# Processor.net
KiCad netlist of a schematic drawn in Altium Designer
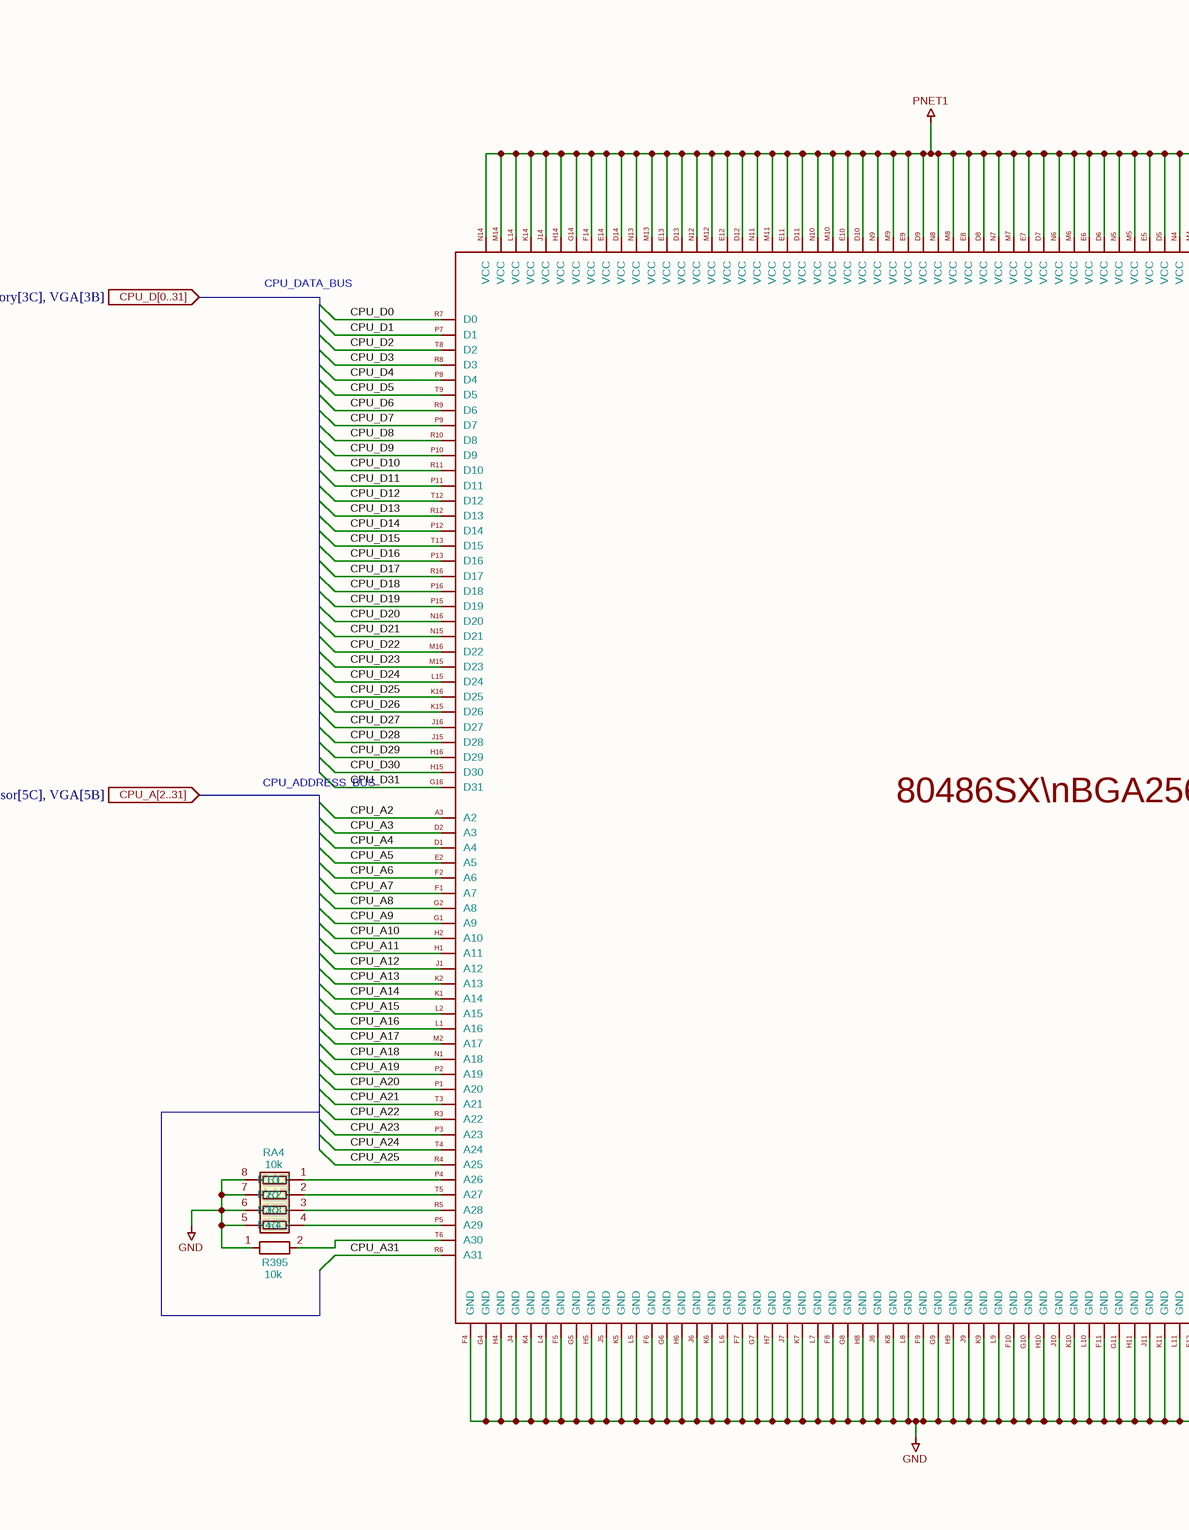
[diagram p0: Processor.SchDoc, left]
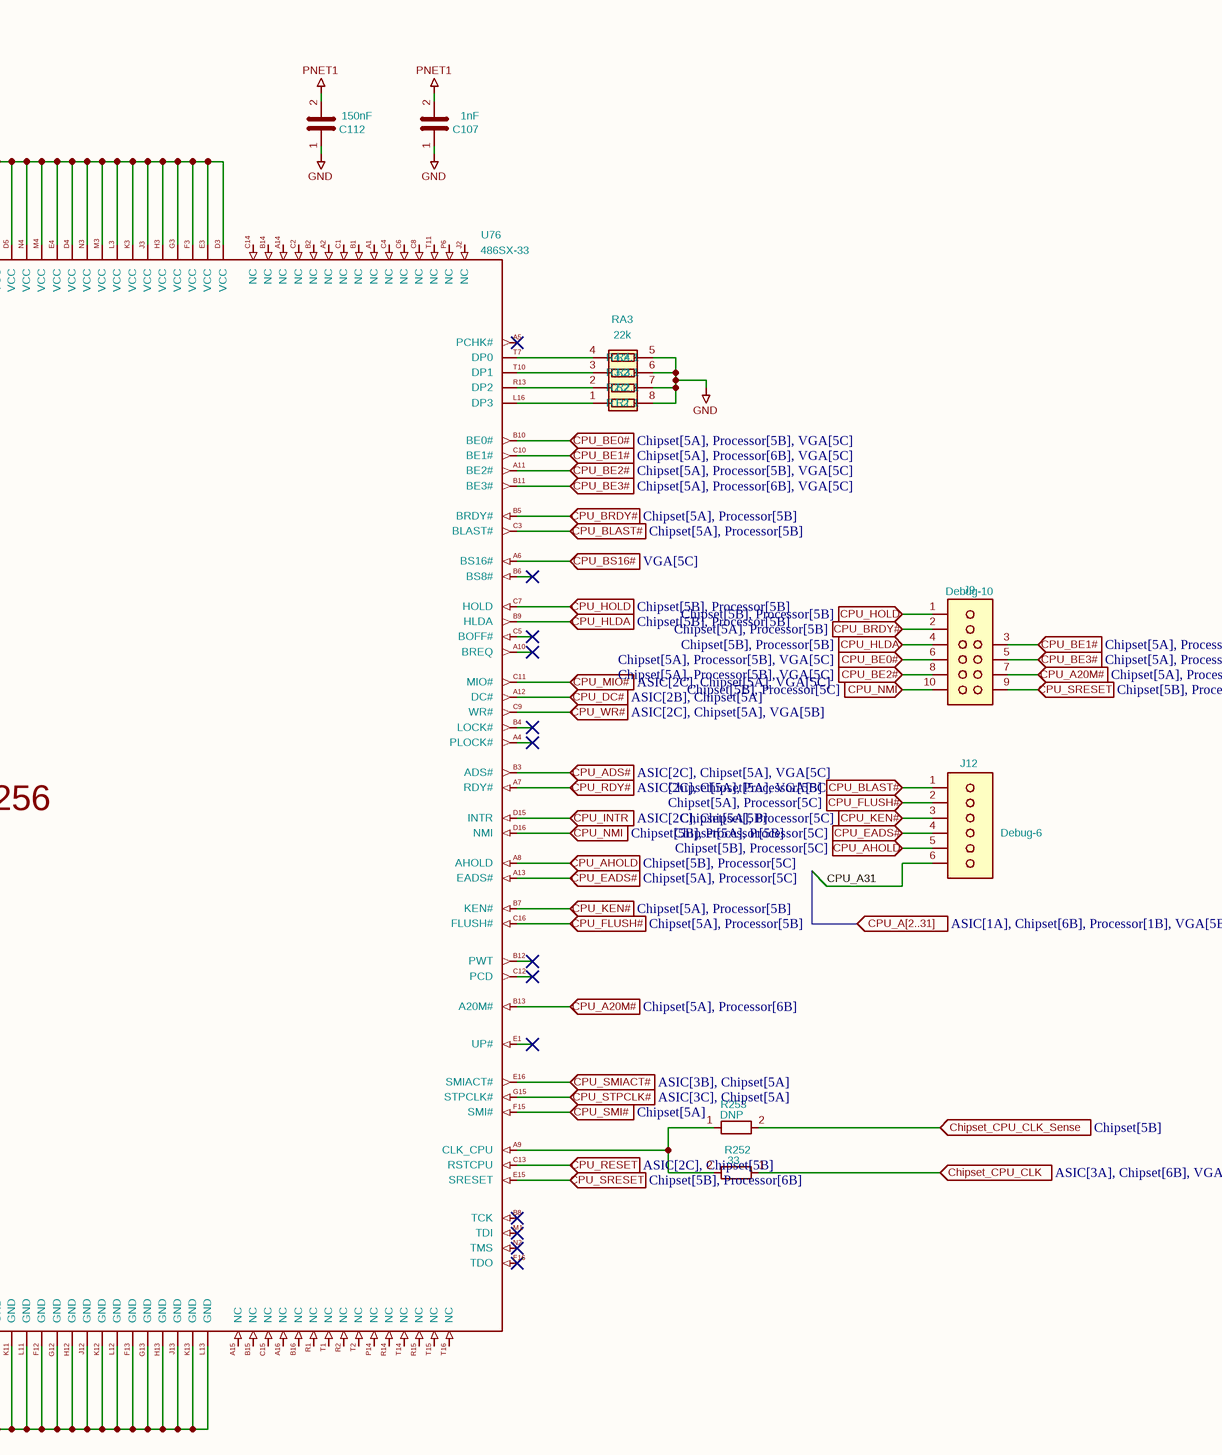
[diagram p1: Processor.SchDoc, right]

(export (version "E")
  (design (tool "Eeschema 10.0.6"))
  (components
    (comp (ref "C107") (value "1nF") (footprint "C_0402_1005Metric") (libsource (lib "Device") (part "C")))
    (comp (ref "C112") (value "150nF") (footprint "C_0402_1005Metric") (libsource (lib "Device") (part "C")))
    (comp (ref "J9") (value "Debug-10") (footprint "Debug-10") (libsource (lib "PC110") (part "CPU_Debug10")))
    (comp (ref "J12") (value "Debug-6") (footprint "Debug-6") (libsource (lib "PC110") (part "CPU_Debug6")))
    (comp (ref "R252") (value "33") (footprint "R_0402_1005Metric") (libsource (lib "Device") (part "R")))
    (comp (ref "R253") (value "DNP") (footprint "R_0402_1005Metric") (libsource (lib "") (part "R_1")))
    (comp (ref "R395") (value "10k") (footprint "R_0402_1005Metric") (libsource (lib "") (part "R_2")))
    (comp (ref "RA3") (value "22k") (footprint "R-array") (libsource (lib "Device") (part "R_Pack04")))
    (comp (ref "RA4") (value "10k") (footprint "R-array") (libsource (lib "") (part "R_Pack04_1")))
    (comp (ref "U76") (value "486SX-33") (footprint "BGA-256") (libsource (lib "PC110") (part "80486SX")))
  )
  (nets
    (net (code "6") (name "/CPU_A2") (class "Default")
      (node (ref "U76") (pin "A3") (pinfunction "A2_A3") (pintype "bidirectional"))
    )
    (net (code "7") (name "/CPU_A3") (class "Default")
      (node (ref "U76") (pin "D2") (pinfunction "A3_D2") (pintype "bidirectional"))
    )
    (net (code "8") (name "/CPU_A4") (class "Default")
      (node (ref "U76") (pin "D1") (pinfunction "A4_D1") (pintype "bidirectional"))
    )
    (net (code "9") (name "/CPU_A5") (class "Default")
      (node (ref "U76") (pin "E2") (pinfunction "A5_E2") (pintype "bidirectional"))
    )
    (net (code "10") (name "/CPU_A6") (class "Default")
      (node (ref "U76") (pin "F2") (pinfunction "A6_F2") (pintype "bidirectional"))
    )
    (net (code "11") (name "/CPU_A7") (class "Default")
      (node (ref "U76") (pin "F1") (pinfunction "A7_F1") (pintype "bidirectional"))
    )
    (net (code "12") (name "/CPU_A8") (class "Default")
      (node (ref "U76") (pin "G2") (pinfunction "A8_G2") (pintype "bidirectional"))
    )
    (net (code "13") (name "/CPU_A9") (class "Default")
      (node (ref "U76") (pin "G1") (pinfunction "A9_G1") (pintype "bidirectional"))
    )
    (net (code "14") (name "/CPU_A10") (class "Default")
      (node (ref "U76") (pin "H2") (pinfunction "A10_H2") (pintype "bidirectional"))
    )
    (net (code "15") (name "/CPU_A11") (class "Default")
      (node (ref "U76") (pin "H1") (pinfunction "A11_H1") (pintype "bidirectional"))
    )
    (net (code "16") (name "/CPU_A12") (class "Default")
      (node (ref "U76") (pin "J1") (pinfunction "A12_J1") (pintype "bidirectional"))
    )
    (net (code "17") (name "/CPU_A13") (class "Default")
      (node (ref "U76") (pin "K2") (pinfunction "A13_K2") (pintype "bidirectional"))
    )
    (net (code "18") (name "/CPU_A14") (class "Default")
      (node (ref "U76") (pin "K1") (pinfunction "A14_K1") (pintype "bidirectional"))
    )
    (net (code "19") (name "/CPU_A15") (class "Default")
      (node (ref "U76") (pin "L2") (pinfunction "A15_L2") (pintype "bidirectional"))
    )
    (net (code "20") (name "/CPU_A16") (class "Default")
      (node (ref "U76") (pin "L1") (pinfunction "A16_L1") (pintype "bidirectional"))
    )
    (net (code "21") (name "/CPU_A17") (class "Default")
      (node (ref "U76") (pin "M2") (pinfunction "A17_M2") (pintype "bidirectional"))
    )
    (net (code "22") (name "/CPU_A18") (class "Default")
      (node (ref "U76") (pin "N1") (pinfunction "A18_N1") (pintype "bidirectional"))
    )
    (net (code "23") (name "/CPU_A19") (class "Default")
      (node (ref "U76") (pin "P2") (pinfunction "A19_P2") (pintype "bidirectional"))
    )
    (net (code "24") (name "/CPU_A20") (class "Default")
      (node (ref "U76") (pin "P1") (pinfunction "A20_P1") (pintype "bidirectional"))
    )
    (net (code "25") (name "/CPU_A20M#") (class "Default")
      (node (ref "J9") (pin "7") (pinfunction "7_7") (pintype "passive"))
      (node (ref "U76") (pin "B13") (pinfunction "A20M#_B13") (pintype "input"))
    )
    (net (code "26") (name "/CPU_A21") (class "Default")
      (node (ref "U76") (pin "T3") (pinfunction "A21_T3") (pintype "bidirectional"))
    )
    (net (code "27") (name "/CPU_A22") (class "Default")
      (node (ref "U76") (pin "R3") (pinfunction "A22_R3") (pintype "bidirectional"))
    )
    (net (code "28") (name "/CPU_A23") (class "Default")
      (node (ref "U76") (pin "P3") (pinfunction "A23_P3") (pintype "bidirectional"))
    )
    (net (code "29") (name "/CPU_A24") (class "Default")
      (node (ref "U76") (pin "T4") (pinfunction "A24_T4") (pintype "bidirectional"))
    )
    (net (code "30") (name "/CPU_A25") (class "Default")
      (node (ref "U76") (pin "R4") (pinfunction "A25_R4") (pintype "bidirectional"))
    )
    (net (code "31") (name "/CPU_A31") (class "Default")
      (node (ref "J12") (pin "6") (pinfunction "6_6") (pintype "passive"))
      (node (ref "U76") (pin "R6") (pinfunction "A31_R6") (pintype "bidirectional"))
    )
    (net (code "32") (name "/CPU_ADS#") (class "Default")
      (node (ref "U76") (pin "B3") (pinfunction "ADS#_B3") (pintype "output"))
    )
    (net (code "33") (name "/CPU_AHOLD") (class "Default")
      (node (ref "J12") (pin "5") (pinfunction "5_5") (pintype "passive"))
      (node (ref "U76") (pin "A8") (pinfunction "AHOLD_A8") (pintype "input"))
    )
    (net (code "35") (name "/CPU_BE0#") (class "Default")
      (node (ref "J9") (pin "6") (pinfunction "6_6") (pintype "passive"))
      (node (ref "U76") (pin "B10") (pinfunction "BE0#_B10") (pintype "output"))
    )
    (net (code "36") (name "/CPU_BE1#") (class "Default")
      (node (ref "J9") (pin "3") (pinfunction "3_3") (pintype "passive"))
      (node (ref "U76") (pin "C10") (pinfunction "BE1#_C10") (pintype "output"))
    )
    (net (code "37") (name "/CPU_BE2#") (class "Default")
      (node (ref "J9") (pin "8") (pinfunction "8_8") (pintype "passive"))
      (node (ref "U76") (pin "A11") (pinfunction "BE2#_A11") (pintype "output"))
    )
    (net (code "38") (name "/CPU_BE3#") (class "Default")
      (node (ref "J9") (pin "5") (pinfunction "5_5") (pintype "passive"))
      (node (ref "U76") (pin "B11") (pinfunction "BE3#_B11") (pintype "output"))
    )
    (net (code "39") (name "/CPU_BLAST#") (class "Default")
      (node (ref "J12") (pin "1") (pinfunction "1_1") (pintype "passive"))
      (node (ref "U76") (pin "C3") (pinfunction "BLAST#_C3") (pintype "output"))
    )
    (net (code "40") (name "/CPU_BRDY#") (class "Default")
      (node (ref "J9") (pin "2") (pinfunction "2_2") (pintype "passive"))
      (node (ref "U76") (pin "B5") (pinfunction "BRDY#_B5") (pintype "input"))
    )
    (net (code "41") (name "/CPU_BS16#") (class "Default")
      (node (ref "U76") (pin "A6") (pinfunction "BS16#_A6") (pintype "input"))
    )
    (net (code "42") (name "/CPU_D0") (class "Default")
      (node (ref "U76") (pin "R7") (pinfunction "D0_R7") (pintype "bidirectional"))
    )
    (net (code "43") (name "/CPU_D1") (class "Default")
      (node (ref "U76") (pin "P7") (pinfunction "D1_P7") (pintype "bidirectional"))
    )
    (net (code "44") (name "/CPU_D2") (class "Default")
      (node (ref "U76") (pin "T8") (pinfunction "D2_T8") (pintype "bidirectional"))
    )
    (net (code "45") (name "/CPU_D3") (class "Default")
      (node (ref "U76") (pin "R8") (pinfunction "D3_R8") (pintype "bidirectional"))
    )
    (net (code "46") (name "/CPU_D4") (class "Default")
      (node (ref "U76") (pin "P8") (pinfunction "D4_P8") (pintype "bidirectional"))
    )
    (net (code "47") (name "/CPU_D5") (class "Default")
      (node (ref "U76") (pin "T9") (pinfunction "D5_T9") (pintype "bidirectional"))
    )
    (net (code "48") (name "/CPU_D6") (class "Default")
      (node (ref "U76") (pin "R9") (pinfunction "D6_R9") (pintype "bidirectional"))
    )
    (net (code "49") (name "/CPU_D7") (class "Default")
      (node (ref "U76") (pin "P9") (pinfunction "D7_P9") (pintype "bidirectional"))
    )
    (net (code "50") (name "/CPU_D8") (class "Default")
      (node (ref "U76") (pin "R10") (pinfunction "D8_R10") (pintype "bidirectional"))
    )
    (net (code "51") (name "/CPU_D9") (class "Default")
      (node (ref "U76") (pin "P10") (pinfunction "D9_P10") (pintype "bidirectional"))
    )
    (net (code "52") (name "/CPU_D10") (class "Default")
      (node (ref "U76") (pin "R11") (pinfunction "D10_R11") (pintype "bidirectional"))
    )
    (net (code "53") (name "/CPU_D11") (class "Default")
      (node (ref "U76") (pin "P11") (pinfunction "D11_P11") (pintype "bidirectional"))
    )
    (net (code "54") (name "/CPU_D12") (class "Default")
      (node (ref "U76") (pin "T12") (pinfunction "D12_T12") (pintype "bidirectional"))
    )
    (net (code "55") (name "/CPU_D13") (class "Default")
      (node (ref "U76") (pin "R12") (pinfunction "D13_R12") (pintype "bidirectional"))
    )
    (net (code "56") (name "/CPU_D14") (class "Default")
      (node (ref "U76") (pin "P12") (pinfunction "D14_P12") (pintype "bidirectional"))
    )
    (net (code "57") (name "/CPU_D15") (class "Default")
      (node (ref "U76") (pin "T13") (pinfunction "D15_T13") (pintype "bidirectional"))
    )
    (net (code "58") (name "/CPU_D16") (class "Default")
      (node (ref "U76") (pin "P13") (pinfunction "D16_P13") (pintype "bidirectional"))
    )
    (net (code "59") (name "/CPU_D17") (class "Default")
      (node (ref "U76") (pin "R16") (pinfunction "D17_R16") (pintype "bidirectional"))
    )
    (net (code "60") (name "/CPU_D18") (class "Default")
      (node (ref "U76") (pin "P16") (pinfunction "D18_P16") (pintype "bidirectional"))
    )
    (net (code "61") (name "/CPU_D19") (class "Default")
      (node (ref "U76") (pin "P15") (pinfunction "D19_P15") (pintype "bidirectional"))
    )
    (net (code "62") (name "/CPU_D20") (class "Default")
      (node (ref "U76") (pin "N16") (pinfunction "D20_N16") (pintype "bidirectional"))
    )
    (net (code "63") (name "/CPU_D21") (class "Default")
      (node (ref "U76") (pin "N15") (pinfunction "D21_N15") (pintype "bidirectional"))
    )
    (net (code "64") (name "/CPU_D22") (class "Default")
      (node (ref "U76") (pin "M16") (pinfunction "D22_M16") (pintype "bidirectional"))
    )
    (net (code "65") (name "/CPU_D23") (class "Default")
      (node (ref "U76") (pin "M15") (pinfunction "D23_M15") (pintype "bidirectional"))
    )
    (net (code "66") (name "/CPU_D24") (class "Default")
      (node (ref "U76") (pin "L15") (pinfunction "D24_L15") (pintype "bidirectional"))
    )
    (net (code "67") (name "/CPU_D25") (class "Default")
      (node (ref "U76") (pin "K16") (pinfunction "D25_K16") (pintype "bidirectional"))
    )
    (net (code "68") (name "/CPU_D26") (class "Default")
      (node (ref "U76") (pin "K15") (pinfunction "D26_K15") (pintype "bidirectional"))
    )
    (net (code "69") (name "/CPU_D27") (class "Default")
      (node (ref "U76") (pin "J16") (pinfunction "D27_J16") (pintype "bidirectional"))
    )
    (net (code "70") (name "/CPU_D28") (class "Default")
      (node (ref "U76") (pin "J15") (pinfunction "D28_J15") (pintype "bidirectional"))
    )
    (net (code "71") (name "/CPU_D29") (class "Default")
      (node (ref "U76") (pin "H16") (pinfunction "D29_H16") (pintype "bidirectional"))
    )
    (net (code "72") (name "/CPU_D30") (class "Default")
      (node (ref "U76") (pin "H15") (pinfunction "D30_H15") (pintype "bidirectional"))
    )
    (net (code "73") (name "/CPU_D31") (class "Default")
      (node (ref "U76") (pin "G16") (pinfunction "D31_G16") (pintype "bidirectional"))
    )
    (net (code "74") (name "/CPU_DC#") (class "Default")
      (node (ref "U76") (pin "A12") (pinfunction "DC#_A12") (pintype "output"))
    )
    (net (code "76") (name "/CPU_EADS#") (class "Default")
      (node (ref "J12") (pin "4") (pinfunction "4_4") (pintype "passive"))
      (node (ref "U76") (pin "A13") (pinfunction "EADS#_A13") (pintype "input"))
    )
    (net (code "77") (name "/CPU_FLUSH#") (class "Default")
      (node (ref "J12") (pin "2") (pinfunction "2_2") (pintype "passive"))
      (node (ref "U76") (pin "C16") (pinfunction "FLUSH#_C16") (pintype "input"))
    )
    (net (code "78") (name "/CPU_HLDA") (class "Default")
      (node (ref "J9") (pin "4") (pinfunction "4_4") (pintype "passive"))
      (node (ref "U76") (pin "B9") (pinfunction "HLDA_B9") (pintype "output"))
    )
    (net (code "79") (name "/CPU_HOLD") (class "Default")
      (node (ref "J9") (pin "1") (pinfunction "1_1") (pintype "passive"))
      (node (ref "U76") (pin "C7") (pinfunction "HOLD_C7") (pintype "input"))
    )
    (net (code "80") (name "/CPU_INTR") (class "Default")
      (node (ref "U76") (pin "D15") (pinfunction "INTR_D15") (pintype "input"))
    )
    (net (code "81") (name "/CPU_KEN#") (class "Default")
      (node (ref "J12") (pin "3") (pinfunction "3_3") (pintype "passive"))
      (node (ref "U76") (pin "B7") (pinfunction "KEN#_B7") (pintype "input"))
    )
    (net (code "82") (name "/CPU_MIO#") (class "Default")
      (node (ref "U76") (pin "C11") (pinfunction "MIO#_C11") (pintype "output"))
    )
    (net (code "83") (name "/CPU_NMI") (class "Default")
      (node (ref "J9") (pin "10") (pinfunction "10_10") (pintype "passive"))
      (node (ref "U76") (pin "D16") (pinfunction "NMI_D16") (pintype "input"))
    )
    (net (code "84") (name "/CPU_RDY#") (class "Default")
      (node (ref "U76") (pin "A7") (pinfunction "RDY#_A7") (pintype "input"))
    )
    (net (code "85") (name "/CPU_RESET") (class "Default")
      (node (ref "U76") (pin "C13") (pinfunction "RSTCPU_C13") (pintype "input"))
    )
    (net (code "86") (name "/CPU_SMI#") (class "Default")
      (node (ref "U76") (pin "F15") (pinfunction "SMI#_F15") (pintype "input"))
    )
    (net (code "87") (name "/CPU_SMIACT#") (class "Default")
      (node (ref "U76") (pin "E16") (pinfunction "SMIACT#_E16") (pintype "output"))
    )
    (net (code "88") (name "/CPU_SRESET") (class "Default")
      (node (ref "J9") (pin "9") (pinfunction "9_9") (pintype "passive"))
      (node (ref "U76") (pin "E15") (pinfunction "SRESET_E15") (pintype "input"))
    )
    (net (code "89") (name "/CPU_STPCLK#") (class "Default")
      (node (ref "U76") (pin "G15") (pinfunction "STPCLK#_G15") (pintype "input"))
    )
    (net (code "90") (name "/CPU_WR#") (class "Default")
      (node (ref "U76") (pin "C9") (pinfunction "WR#_C9") (pintype "output"))
    )
    (net (code "91") (name "/Chipset_CPU_CLK") (class "Default")
      (node (ref "R252") (pin "1") (pinfunction "1_1") (pintype "passive"))
    )
    (net (code "92") (name "/Chipset_CPU_CLK_Sense") (class "Default")
      (node (ref "R253") (pin "2") (pinfunction "2_2") (pintype "passive"))
    )
    (net (code "93") (name "GND") (class "Default")
      (node (ref "C107") (pin "1") (pinfunction "1_1") (pintype "passive"))
      (node (ref "C112") (pin "1") (pinfunction "1_1") (pintype "passive"))
      (node (ref "R395") (pin "1") (pinfunction "1_1") (pintype "passive"))
      (node (ref "RA3") (pin "5") (pinfunction "R4.2_5") (pintype "passive"))
      (node (ref "RA3") (pin "6") (pinfunction "R3.2_6") (pintype "passive"))
      (node (ref "RA3") (pin "7") (pinfunction "R2.2_7") (pintype "passive"))
      (node (ref "RA3") (pin "8") (pinfunction "R1.2_8") (pintype "passive"))
      (node (ref "RA4") (pin "5") (pinfunction "R4.2_5") (pintype "passive"))
      (node (ref "RA4") (pin "6") (pinfunction "R3.2_6") (pintype "passive"))
      (node (ref "RA4") (pin "7") (pinfunction "R2.2_7") (pintype "passive"))
      (node (ref "RA4") (pin "8") (pinfunction "R1.2_8") (pintype "passive"))
      (node (ref "U76") (pin "F10") (pinfunction "GND_F10") (pintype "power_in"))
      (node (ref "U76") (pin "F11") (pinfunction "GND_F11") (pintype "power_in"))
      (node (ref "U76") (pin "F12") (pinfunction "GND_F12") (pintype "power_in"))
      (node (ref "U76") (pin "F13") (pinfunction "GND_F13") (pintype "power_in"))
      (node (ref "U76") (pin "F4") (pinfunction "GND_F4") (pintype "power_in"))
      (node (ref "U76") (pin "F5") (pinfunction "GND_F5") (pintype "power_in"))
      (node (ref "U76") (pin "F6") (pinfunction "GND_F6") (pintype "power_in"))
      (node (ref "U76") (pin "F7") (pinfunction "GND_F7") (pintype "power_in"))
      (node (ref "U76") (pin "F8") (pinfunction "GND_F8") (pintype "power_in"))
      (node (ref "U76") (pin "F9") (pinfunction "GND_F9") (pintype "power_in"))
      (node (ref "U76") (pin "G10") (pinfunction "GND_G10") (pintype "power_in"))
      (node (ref "U76") (pin "G11") (pinfunction "GND_G11") (pintype "power_in"))
      (node (ref "U76") (pin "G12") (pinfunction "GND_G12") (pintype "power_in"))
      (node (ref "U76") (pin "G13") (pinfunction "GND_G13") (pintype "power_in"))
      (node (ref "U76") (pin "G4") (pinfunction "GND_G4") (pintype "power_in"))
      (node (ref "U76") (pin "G5") (pinfunction "GND_G5") (pintype "power_in"))
      (node (ref "U76") (pin "G6") (pinfunction "GND_G6") (pintype "power_in"))
      (node (ref "U76") (pin "G7") (pinfunction "GND_G7") (pintype "power_in"))
      (node (ref "U76") (pin "G8") (pinfunction "GND_G8") (pintype "power_in"))
      (node (ref "U76") (pin "G9") (pinfunction "GND_G9") (pintype "power_in"))
      (node (ref "U76") (pin "H10") (pinfunction "GND_H10") (pintype "power_in"))
      (node (ref "U76") (pin "H11") (pinfunction "GND_H11") (pintype "power_in"))
      (node (ref "U76") (pin "H12") (pinfunction "GND_H12") (pintype "power_in"))
      (node (ref "U76") (pin "H13") (pinfunction "GND_H13") (pintype "power_in"))
      (node (ref "U76") (pin "H4") (pinfunction "GND_H4") (pintype "power_in"))
      (node (ref "U76") (pin "H5") (pinfunction "GND_H5") (pintype "power_in"))
      (node (ref "U76") (pin "H6") (pinfunction "GND_H6") (pintype "power_in"))
      (node (ref "U76") (pin "H7") (pinfunction "GND_H7") (pintype "power_in"))
      (node (ref "U76") (pin "H8") (pinfunction "GND_H8") (pintype "power_in"))
      (node (ref "U76") (pin "H9") (pinfunction "GND_H9") (pintype "power_in"))
      (node (ref "U76") (pin "J10") (pinfunction "GND_J10") (pintype "power_in"))
      (node (ref "U76") (pin "J11") (pinfunction "GND_J11") (pintype "power_in"))
      (node (ref "U76") (pin "J12") (pinfunction "GND_J12") (pintype "power_in"))
      (node (ref "U76") (pin "J13") (pinfunction "GND_J13") (pintype "power_in"))
      (node (ref "U76") (pin "J4") (pinfunction "GND_J4") (pintype "power_in"))
      (node (ref "U76") (pin "J5") (pinfunction "GND_J5") (pintype "power_in"))
      (node (ref "U76") (pin "J6") (pinfunction "GND_J6") (pintype "power_in"))
      (node (ref "U76") (pin "J7") (pinfunction "GND_J7") (pintype "power_in"))
      (node (ref "U76") (pin "J8") (pinfunction "GND_J8") (pintype "power_in"))
      (node (ref "U76") (pin "J9") (pinfunction "GND_J9") (pintype "power_in"))
      (node (ref "U76") (pin "K10") (pinfunction "GND_K10") (pintype "power_in"))
      (node (ref "U76") (pin "K11") (pinfunction "GND_K11") (pintype "power_in"))
      (node (ref "U76") (pin "K12") (pinfunction "GND_K12") (pintype "power_in"))
      (node (ref "U76") (pin "K13") (pinfunction "GND_K13") (pintype "power_in"))
      (node (ref "U76") (pin "K4") (pinfunction "GND_K4") (pintype "power_in"))
      (node (ref "U76") (pin "K5") (pinfunction "GND_K5") (pintype "power_in"))
      (node (ref "U76") (pin "K6") (pinfunction "GND_K6") (pintype "power_in"))
      (node (ref "U76") (pin "K7") (pinfunction "GND_K7") (pintype "power_in"))
      (node (ref "U76") (pin "K8") (pinfunction "GND_K8") (pintype "power_in"))
      (node (ref "U76") (pin "K9") (pinfunction "GND_K9") (pintype "power_in"))
      (node (ref "U76") (pin "L10") (pinfunction "GND_L10") (pintype "power_in"))
      (node (ref "U76") (pin "L11") (pinfunction "GND_L11") (pintype "power_in"))
      (node (ref "U76") (pin "L12") (pinfunction "GND_L12") (pintype "power_in"))
      (node (ref "U76") (pin "L13") (pinfunction "GND_L13") (pintype "power_in"))
      (node (ref "U76") (pin "L4") (pinfunction "GND_L4") (pintype "power_in"))
      (node (ref "U76") (pin "L5") (pinfunction "GND_L5") (pintype "power_in"))
      (node (ref "U76") (pin "L6") (pinfunction "GND_L6") (pintype "power_in"))
      (node (ref "U76") (pin "L7") (pinfunction "GND_L7") (pintype "power_in"))
      (node (ref "U76") (pin "L8") (pinfunction "GND_L8") (pintype "power_in"))
      (node (ref "U76") (pin "L9") (pinfunction "GND_L9") (pintype "power_in"))
    )
    (net (code "94") (name "Net-(RA3-R1.1)") (class "Default")
      (node (ref "RA3") (pin "1") (pinfunction "R1.1_1") (pintype "passive"))
      (node (ref "U76") (pin "L16") (pinfunction "DP3_L16") (pintype "bidirectional"))
    )
    (net (code "95") (name "Net-(RA3-R2.1)") (class "Default")
      (node (ref "RA3") (pin "2") (pinfunction "R2.1_2") (pintype "passive"))
      (node (ref "U76") (pin "R13") (pinfunction "DP2_R13") (pintype "bidirectional"))
    )
    (net (code "96") (name "Net-(RA3-R3.1)") (class "Default")
      (node (ref "RA3") (pin "3") (pinfunction "R3.1_3") (pintype "passive"))
      (node (ref "U76") (pin "T10") (pinfunction "DP1_T10") (pintype "bidirectional"))
    )
    (net (code "97") (name "Net-(RA3-R4.1)") (class "Default")
      (node (ref "RA3") (pin "4") (pinfunction "R4.1_4") (pintype "passive"))
      (node (ref "U76") (pin "T7") (pinfunction "DP0_T7") (pintype "bidirectional"))
    )
    (net (code "98") (name "Net-(RA4-R1.1)") (class "Default")
      (node (ref "RA4") (pin "1") (pinfunction "R1.1_1") (pintype "passive"))
      (node (ref "U76") (pin "P4") (pinfunction "A26_P4") (pintype "bidirectional"))
    )
    (net (code "99") (name "Net-(RA4-R2.1)") (class "Default")
      (node (ref "RA4") (pin "2") (pinfunction "R2.1_2") (pintype "passive"))
      (node (ref "U76") (pin "T5") (pinfunction "A27_T5") (pintype "bidirectional"))
    )
    (net (code "100") (name "Net-(RA4-R3.1)") (class "Default")
      (node (ref "RA4") (pin "3") (pinfunction "R3.1_3") (pintype "passive"))
      (node (ref "U76") (pin "R5") (pinfunction "A28_R5") (pintype "bidirectional"))
    )
    (net (code "101") (name "Net-(RA4-R4.1)") (class "Default")
      (node (ref "RA4") (pin "4") (pinfunction "R4.1_4") (pintype "passive"))
      (node (ref "U76") (pin "P5") (pinfunction "A29_P5") (pintype "bidirectional"))
    )
    (net (code "102") (name "Net-(U76-A30)") (class "Default")
      (node (ref "R395") (pin "2") (pinfunction "2_2") (pintype "passive"))
      (node (ref "U76") (pin "T6") (pinfunction "A30_T6") (pintype "bidirectional"))
    )
    (net (code "103") (name "Net-(U76-CLK_CPU)") (class "Default")
      (node (ref "R252") (pin "2") (pinfunction "2_2") (pintype "passive"))
      (node (ref "R253") (pin "1") (pinfunction "1_1") (pintype "passive"))
      (node (ref "U76") (pin "A9") (pinfunction "CLK_CPU_A9") (pintype "input"))
    )
    (net (code "104") (name "PNET1") (class "Default")
      (node (ref "C107") (pin "2") (pinfunction "2_2") (pintype "passive"))
      (node (ref "C112") (pin "2") (pinfunction "2_2") (pintype "passive"))
      (node (ref "U76") (pin "D10") (pinfunction "VCC_D10") (pintype "power_in"))
      (node (ref "U76") (pin "D11") (pinfunction "VCC_D11") (pintype "power_in"))
      (node (ref "U76") (pin "D12") (pinfunction "VCC_D12") (pintype "power_in"))
      (node (ref "U76") (pin "D13") (pinfunction "VCC_D13") (pintype "power_in"))
      (node (ref "U76") (pin "D14") (pinfunction "VCC_D14") (pintype "power_in"))
      (node (ref "U76") (pin "D3") (pinfunction "VCC_D3") (pintype "power_in"))
      (node (ref "U76") (pin "D4") (pinfunction "VCC_D4") (pintype "power_in"))
      (node (ref "U76") (pin "D5") (pinfunction "VCC_D5") (pintype "power_in"))
      (node (ref "U76") (pin "D6") (pinfunction "VCC_D6") (pintype "power_in"))
      (node (ref "U76") (pin "D7") (pinfunction "VCC_D7") (pintype "power_in"))
      (node (ref "U76") (pin "D8") (pinfunction "VCC_D8") (pintype "power_in"))
      (node (ref "U76") (pin "D9") (pinfunction "VCC_D9") (pintype "power_in"))
      (node (ref "U76") (pin "E10") (pinfunction "VCC_E10") (pintype "power_in"))
      (node (ref "U76") (pin "E11") (pinfunction "VCC_E11") (pintype "power_in"))
      (node (ref "U76") (pin "E12") (pinfunction "VCC_E12") (pintype "power_in"))
      (node (ref "U76") (pin "E13") (pinfunction "VCC_E13") (pintype "power_in"))
      (node (ref "U76") (pin "E14") (pinfunction "VCC_E14") (pintype "power_in"))
      (node (ref "U76") (pin "E3") (pinfunction "VCC_E3") (pintype "power_in"))
      (node (ref "U76") (pin "E4") (pinfunction "VCC_E4") (pintype "power_in"))
      (node (ref "U76") (pin "E5") (pinfunction "VCC_E5") (pintype "power_in"))
      (node (ref "U76") (pin "E6") (pinfunction "VCC_E6") (pintype "power_in"))
      (node (ref "U76") (pin "E7") (pinfunction "VCC_E7") (pintype "power_in"))
      (node (ref "U76") (pin "E8") (pinfunction "VCC_E8") (pintype "power_in"))
      (node (ref "U76") (pin "E9") (pinfunction "VCC_E9") (pintype "power_in"))
      (node (ref "U76") (pin "F14") (pinfunction "VCC_F14") (pintype "power_in"))
      (node (ref "U76") (pin "F3") (pinfunction "VCC_F3") (pintype "power_in"))
      (node (ref "U76") (pin "G14") (pinfunction "VCC_G14") (pintype "power_in"))
      (node (ref "U76") (pin "G3") (pinfunction "VCC_G3") (pintype "power_in"))
      (node (ref "U76") (pin "H14") (pinfunction "VCC_H14") (pintype "power_in"))
      (node (ref "U76") (pin "H3") (pinfunction "VCC_H3") (pintype "power_in"))
      (node (ref "U76") (pin "J14") (pinfunction "VCC_J14") (pintype "power_in"))
      (node (ref "U76") (pin "J3") (pinfunction "VCC_J3") (pintype "power_in"))
      (node (ref "U76") (pin "K14") (pinfunction "VCC_K14") (pintype "power_in"))
      (node (ref "U76") (pin "K3") (pinfunction "VCC_K3") (pintype "power_in"))
      (node (ref "U76") (pin "L14") (pinfunction "VCC_L14") (pintype "power_in"))
      (node (ref "U76") (pin "L3") (pinfunction "VCC_L3") (pintype "power_in"))
      (node (ref "U76") (pin "M10") (pinfunction "VCC_M10") (pintype "power_in"))
      (node (ref "U76") (pin "M11") (pinfunction "VCC_M11") (pintype "power_in"))
      (node (ref "U76") (pin "M12") (pinfunction "VCC_M12") (pintype "power_in"))
      (node (ref "U76") (pin "M13") (pinfunction "VCC_M13") (pintype "power_in"))
      (node (ref "U76") (pin "M14") (pinfunction "VCC_M14") (pintype "power_in"))
      (node (ref "U76") (pin "M3") (pinfunction "VCC_M3") (pintype "power_in"))
      (node (ref "U76") (pin "M4") (pinfunction "VCC_M4") (pintype "power_in"))
      (node (ref "U76") (pin "M5") (pinfunction "VCC_M5") (pintype "power_in"))
      (node (ref "U76") (pin "M6") (pinfunction "VCC_M6") (pintype "power_in"))
      (node (ref "U76") (pin "M7") (pinfunction "VCC_M7") (pintype "power_in"))
      (node (ref "U76") (pin "M8") (pinfunction "VCC_M8") (pintype "power_in"))
      (node (ref "U76") (pin "M9") (pinfunction "VCC_M9") (pintype "power_in"))
      (node (ref "U76") (pin "N10") (pinfunction "VCC_N10") (pintype "power_in"))
      (node (ref "U76") (pin "N11") (pinfunction "VCC_N11") (pintype "power_in"))
      (node (ref "U76") (pin "N12") (pinfunction "VCC_N12") (pintype "power_in"))
      (node (ref "U76") (pin "N13") (pinfunction "VCC_N13") (pintype "power_in"))
      (node (ref "U76") (pin "N14") (pinfunction "VCC_N14") (pintype "power_in"))
      (node (ref "U76") (pin "N3") (pinfunction "VCC_N3") (pintype "power_in"))
      (node (ref "U76") (pin "N4") (pinfunction "VCC_N4") (pintype "power_in"))
      (node (ref "U76") (pin "N5") (pinfunction "VCC_N5") (pintype "power_in"))
      (node (ref "U76") (pin "N6") (pinfunction "VCC_N6") (pintype "power_in"))
      (node (ref "U76") (pin "N7") (pinfunction "VCC_N7") (pintype "power_in"))
      (node (ref "U76") (pin "N8") (pinfunction "VCC_N8") (pintype "power_in"))
      (node (ref "U76") (pin "N9") (pinfunction "VCC_N9") (pintype "power_in"))
    )
    (net (code "105") (name "unconnected-(U76-BOFF#-PadC5)") (class "Default")
      (node (ref "U76") (pin "C5") (pinfunction "BOFF#_C5") (pintype "input+no_connect"))
    )
    (net (code "106") (name "unconnected-(U76-BREQ-PadA10)") (class "Default")
      (node (ref "U76") (pin "A10") (pinfunction "BREQ_A10") (pintype "output+no_connect"))
    )
    (net (code "107") (name "unconnected-(U76-BS8#-PadB6)") (class "Default")
      (node (ref "U76") (pin "B6") (pinfunction "BS8#_B6") (pintype "input+no_connect"))
    )
    (net (code "108") (name "unconnected-(U76-LOCK#-PadB4)") (class "Default")
      (node (ref "U76") (pin "B4") (pinfunction "LOCK#_B4") (pintype "output+no_connect"))
    )
    (net (code "109") (name "unconnected-(U76-NC-PadA1)") (class "Default")
      (node (ref "U76") (pin "A1") (pinfunction "NC_A1") (pintype "input"))
    )
    (net (code "110") (name "unconnected-(U76-NC-PadA2)") (class "Default")
      (node (ref "U76") (pin "A2") (pinfunction "NC_A2") (pintype "input"))
    )
    (net (code "111") (name "unconnected-(U76-NC-PadA14)") (class "Default")
      (node (ref "U76") (pin "A14") (pinfunction "NC_A14") (pintype "input"))
    )
    (net (code "112") (name "unconnected-(U76-NC-PadA15)") (class "Default")
      (node (ref "U76") (pin "A15") (pinfunction "NC_A15") (pintype "input"))
    )
    (net (code "113") (name "unconnected-(U76-NC-PadA16)") (class "Default")
      (node (ref "U76") (pin "A16") (pinfunction "NC_A16") (pintype "input"))
    )
    (net (code "114") (name "unconnected-(U76-NC-PadB1)") (class "Default")
      (node (ref "U76") (pin "B1") (pinfunction "NC_B1") (pintype "input"))
    )
    (net (code "115") (name "unconnected-(U76-NC-PadB2)") (class "Default")
      (node (ref "U76") (pin "B2") (pinfunction "NC_B2") (pintype "input"))
    )
    (net (code "116") (name "unconnected-(U76-NC-PadB14)") (class "Default")
      (node (ref "U76") (pin "B14") (pinfunction "NC_B14") (pintype "input"))
    )
    (net (code "117") (name "unconnected-(U76-NC-PadB15)") (class "Default")
      (node (ref "U76") (pin "B15") (pinfunction "NC_B15") (pintype "input"))
    )
    (net (code "118") (name "unconnected-(U76-NC-PadB16)") (class "Default")
      (node (ref "U76") (pin "B16") (pinfunction "NC_B16") (pintype "input"))
    )
    (net (code "119") (name "unconnected-(U76-NC-PadC1)") (class "Default")
      (node (ref "U76") (pin "C1") (pinfunction "NC_C1") (pintype "input"))
    )
    (net (code "120") (name "unconnected-(U76-NC-PadC2)") (class "Default")
      (node (ref "U76") (pin "C2") (pinfunction "NC_C2") (pintype "input"))
    )
    (net (code "121") (name "unconnected-(U76-NC-PadC4)") (class "Default")
      (node (ref "U76") (pin "C4") (pinfunction "NC_C4") (pintype "input"))
    )
    (net (code "122") (name "unconnected-(U76-NC-PadC6)") (class "Default")
      (node (ref "U76") (pin "C6") (pinfunction "NC_C6") (pintype "input"))
    )
    (net (code "123") (name "unconnected-(U76-NC-PadC8)") (class "Default")
      (node (ref "U76") (pin "C8") (pinfunction "NC_C8") (pintype "input"))
    )
    (net (code "124") (name "unconnected-(U76-NC-PadC14)") (class "Default")
      (node (ref "U76") (pin "C14") (pinfunction "NC_C14") (pintype "input"))
    )
    (net (code "125") (name "unconnected-(U76-NC-PadC15)") (class "Default")
      (node (ref "U76") (pin "C15") (pinfunction "NC_C15") (pintype "input"))
    )
    (net (code "126") (name "unconnected-(U76-NC-PadJ2)") (class "Default")
      (node (ref "U76") (pin "J2") (pinfunction "NC_J2") (pintype "input"))
    )
    (net (code "127") (name "unconnected-(U76-NC-PadP6)") (class "Default")
      (node (ref "U76") (pin "P6") (pinfunction "NC_P6") (pintype "input"))
    )
    (net (code "128") (name "unconnected-(U76-NC-PadP14)") (class "Default")
      (node (ref "U76") (pin "P14") (pinfunction "NC_P14") (pintype "input"))
    )
    (net (code "129") (name "unconnected-(U76-NC-PadR1)") (class "Default")
      (node (ref "U76") (pin "R1") (pinfunction "NC_R1") (pintype "input"))
    )
    (net (code "130") (name "unconnected-(U76-NC-PadR2)") (class "Default")
      (node (ref "U76") (pin "R2") (pinfunction "NC_R2") (pintype "input"))
    )
    (net (code "131") (name "unconnected-(U76-NC-PadR14)") (class "Default")
      (node (ref "U76") (pin "R14") (pinfunction "NC_R14") (pintype "input"))
    )
    (net (code "132") (name "unconnected-(U76-NC-PadR15)") (class "Default")
      (node (ref "U76") (pin "R15") (pinfunction "NC_R15") (pintype "input"))
    )
    (net (code "133") (name "unconnected-(U76-NC-PadT1)") (class "Default")
      (node (ref "U76") (pin "T1") (pinfunction "NC_T1") (pintype "input"))
    )
    (net (code "134") (name "unconnected-(U76-NC-PadT2)") (class "Default")
      (node (ref "U76") (pin "T2") (pinfunction "NC_T2") (pintype "input"))
    )
    (net (code "135") (name "unconnected-(U76-NC-PadT11)") (class "Default")
      (node (ref "U76") (pin "T11") (pinfunction "NC_T11") (pintype "input"))
    )
    (net (code "136") (name "unconnected-(U76-NC-PadT14)") (class "Default")
      (node (ref "U76") (pin "T14") (pinfunction "NC_T14") (pintype "input"))
    )
    (net (code "137") (name "unconnected-(U76-NC-PadT15)") (class "Default")
      (node (ref "U76") (pin "T15") (pinfunction "NC_T15") (pintype "input"))
    )
    (net (code "138") (name "unconnected-(U76-NC-PadT16)") (class "Default")
      (node (ref "U76") (pin "T16") (pinfunction "NC_T16") (pintype "input"))
    )
    (net (code "139") (name "unconnected-(U76-PCD-PadC12)") (class "Default")
      (node (ref "U76") (pin "C12") (pinfunction "PCD_C12") (pintype "output+no_connect"))
    )
    (net (code "140") (name "unconnected-(U76-PCHK#-PadA5)") (class "Default")
      (node (ref "U76") (pin "A5") (pinfunction "PCHK#_A5") (pintype "output+no_connect"))
    )
    (net (code "141") (name "unconnected-(U76-PLOCK#-PadA4)") (class "Default")
      (node (ref "U76") (pin "A4") (pinfunction "PLOCK#_A4") (pintype "output+no_connect"))
    )
    (net (code "142") (name "unconnected-(U76-PWT-PadB12)") (class "Default")
      (node (ref "U76") (pin "B12") (pinfunction "PWT_B12") (pintype "output+no_connect"))
    )
    (net (code "143") (name "unconnected-(U76-TCK-PadB8)") (class "Default")
      (node (ref "U76") (pin "B8") (pinfunction "TCK_B8") (pintype "input+no_connect"))
    )
    (net (code "144") (name "unconnected-(U76-TDI-PadM1)") (class "Default")
      (node (ref "U76") (pin "M1") (pinfunction "TDI_M1") (pintype "input+no_connect"))
    )
    (net (code "145") (name "unconnected-(U76-TDO-PadF16)") (class "Default")
      (node (ref "U76") (pin "F16") (pinfunction "TDO_F16") (pintype "input+no_connect"))
    )
    (net (code "146") (name "unconnected-(U76-TMS-PadN2)") (class "Default")
      (node (ref "U76") (pin "N2") (pinfunction "TMS_N2") (pintype "input+no_connect"))
    )
    (net (code "147") (name "unconnected-(U76-UP#-PadE1)") (class "Default")
      (node (ref "U76") (pin "E1") (pinfunction "UP#_E1") (pintype "input+no_connect"))
    )
  )
)
